# Schematic.net
KiCad netlist of a schematic drawn in Altium Designer
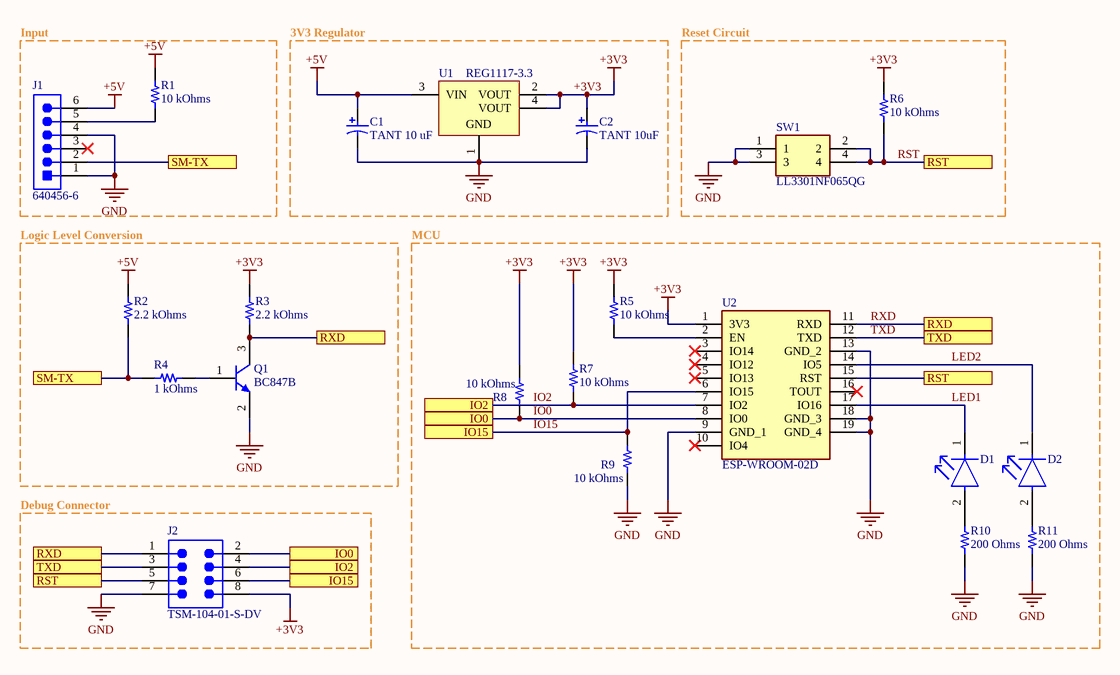
[diagram p0: Schematic.SchDoc]

(export (version "E")
  (design (tool "Eeschema 10.0.6"))
  (components
    (comp (ref "C1")
      (value "TANT 10 uF")
      (footprint "CAPMP3217X18-T_V")
      (description "Standard Tantalum, 10 uF, +/- 10%, 16 V, -55 to 125 degC, 2-Pin SMD (1206), RoHS, Tape and Reel")
      (libsource (lib "Altium Content Vault") (part "CAP-P-2"))
    )
    (comp (ref "C2")
      (value "TANT 10uF")
      (footprint "CAPMP3217X18-T_V")
      (description "Standard Tantalum, 10 uF, +/- 10%, 16 V, -55 to 125 degC, 2-Pin SMD (1206), RoHS, Tape and Reel")
      (libsource (lib "Altium Content Vault") (part "CAP-P-2"))
    )
    (comp (ref "D1")
      (value "LTST-C190GKT")
      (footprint "FP-LTST-C190GKT-MFG")
      (description "LED GREEN CLEAR CHIP SMD")
      (fields (field (name "VOLTAGE") "2V"))
      (libsource (lib "Altium Content Vault") (part "8706943c75ba83719d021d2fdc84c58"))
    )
    (comp (ref "D2")
      (value "LTST-C190GKT")
      (footprint "FP-LTST-C190GKT-MFG")
      (description "LED GREEN CLEAR CHIP SMD")
      (fields (field (name "VOLTAGE") "2V"))
      (libsource (lib "Altium Content Vault") (part "8706943c75ba83719d021d2fdc84c58"))
    )
    (comp (ref "J1")
      (value "640456-6")
      (footprint "TECO-640456-6_V")
      (fields (field (name "MANUFACTURER") "TE Connectivity"))
      (libsource (lib "Altium Content Vault") (part "CN-1P-M-R6"))
    )
    (comp (ref "J2")
      (value "TSM-104-01-S-DV")
      (footprint "SMTC-TSM-104-01-X-DV")
      (description "0.025\" SQ Post Header, Surface Mount, Vertical, -55 to 125 degC, 2.54 mm Pitch, 8-Pin, Male, RoHS")
      (fields (field (name "MANUFACTURER") "Samtec"))
      (libsource (lib "Altium Content Vault") (part "SMTC-TSM-104-01-X-X"))
    )
    (comp (ref "Q1")
      (value "BC847B")
      (footprint "INF-SOT23_M")
      (description "NPN Silicon AF Transistor, 45 V VCEO, 100 mA IC, SOT23, Reel, Green")
      (fields (field (name "MANUFACTURER") "Infineon"))
      (libsource (lib "Altium Content Vault") (part "INF-BJTNPN-BEC-3"))
    )
    (comp (ref "R1")
      (value "10 kOhms")
      (footprint "RES 0805_2012")
      (description "RES 10K OHM 0.1% 1/10W 0805")
      (fields
        (field (name "PART NUMBER") "RNCS0805BKE10K0")
        (field (name "MANUFACTURER") "Stackpole Electronics Inc")
      )
      (libsource (lib "Celestial Altium Library - altium_library") (part "Resistor"))
    )
    (comp (ref "R2")
      (value "2.2 kOhms")
      (footprint "RES 0805_2012")
      (description "RES SMD 2.2K OHM 5% 1/4W 0805")
      (fields (field (name "PART NUMBER") "SR0805JR-7W2K2L") (field (name "MANUFACTURER") "Yageo"))
      (libsource (lib "Celestial Altium Library - altium_library") (part "Resistor"))
    )
    (comp (ref "R3")
      (value "2.2 kOhms")
      (footprint "RES 0805_2012")
      (description "RES SMD 2.2K OHM 5% 1/4W 0805")
      (fields (field (name "PART NUMBER") "SR0805JR-7W2K2L") (field (name "MANUFACTURER") "Yageo"))
      (libsource (lib "Celestial Altium Library - altium_library") (part "Resistor"))
    )
    (comp (ref "R4")
      (value "1 kOhms")
      (footprint "RES 0805_2012")
      (description "RES 1K OHM 0.1% 1/10W 0805")
      (fields
        (field (name "PART NUMBER") "RNCS0805BKE1K00")
        (field (name "MANUFACTURER") "Stackpole Electronics Inc")
      )
      (libsource (lib "Celestial Altium Library - altium_library") (part "Resistor"))
    )
    (comp (ref "R5")
      (value "10 kOhms")
      (footprint "RES 0805_2012")
      (description "RES 10K OHM 0.1% 1/10W 0805")
      (fields
        (field (name "PART NUMBER") "RNCS0805BKE10K0")
        (field (name "MANUFACTURER") "Stackpole Electronics Inc")
      )
      (libsource (lib "Celestial Altium Library - altium_library") (part "Resistor"))
    )
    (comp (ref "R6")
      (value "10 kOhms")
      (footprint "RES 0805_2012")
      (description "RES 10K OHM 0.1% 1/10W 0805")
      (fields
        (field (name "PART NUMBER") "RNCS0805BKE10K0")
        (field (name "MANUFACTURER") "Stackpole Electronics Inc")
      )
      (libsource (lib "Celestial Altium Library - altium_library") (part "Resistor"))
    )
    (comp (ref "R7")
      (value "10 kOhms")
      (footprint "RES 0805_2012")
      (description "RES 10K OHM 0.1% 1/10W 0805")
      (fields
        (field (name "PART NUMBER") "RNCS0805BKE10K0")
        (field (name "MANUFACTURER") "Stackpole Electronics Inc")
      )
      (libsource (lib "Celestial Altium Library - altium_library") (part "Resistor"))
    )
    (comp (ref "R8")
      (value "10 kOhms")
      (footprint "RES 0805_2012")
      (description "RES 10K OHM 0.1% 1/10W 0805")
      (fields
        (field (name "PART NUMBER") "RNCS0805BKE10K0")
        (field (name "MANUFACTURER") "Stackpole Electronics Inc")
      )
      (libsource (lib "Celestial Altium Library - altium_library") (part "Resistor"))
    )
    (comp (ref "R9")
      (value "10 kOhms")
      (footprint "RES 0805_2012")
      (description "RES 10K OHM 0.1% 1/10W 0805")
      (fields
        (field (name "PART NUMBER") "RNCS0805BKE10K0")
        (field (name "MANUFACTURER") "Stackpole Electronics Inc")
      )
      (libsource (lib "Celestial Altium Library - altium_library") (part "Resistor"))
    )
    (comp (ref "R10")
      (value "200 Ohms")
      (footprint "RES 0805_2012")
      (description "RES SMD 200 OHM 0.5% 1/4W 0805")
      (fields
        (field (name "PART NUMBER") "ERJ-PB6D2000V")
        (field (name "MANUFACTURER") "Panasonic Electronic Components")
      )
      (libsource (lib "Celestial Altium Library - altium_library") (part "Resistor"))
    )
    (comp (ref "R11")
      (value "200 Ohms")
      (footprint "RES 0805_2012")
      (description "RES SMD 200 OHM 0.5% 1/4W 0805")
      (fields
        (field (name "PART NUMBER") "ERJ-PB6D2000V")
        (field (name "MANUFACTURER") "Panasonic Electronic Components")
      )
      (libsource (lib "Celestial Altium Library - altium_library") (part "Resistor"))
    )
    (comp (ref "SW1")
      (value "LL3301NF065QG")
      (footprint "SamacSys:LL3301NF065QG")
      (description "Switch")
      (fields (field (name "MOUSER2 PART NUMBER") "612-LL3301NF065QG"))
      (libsource (lib "SamacSys") (part "LL3301NF065QG"))
    )
    (comp (ref "U1")
      (value "REG1117-3.3")
      (footprint "DCY0004A_M")
      (fields (field (name "MANUFACTURER") "Texas Instruments"))
      (libsource (lib "Altium Content Vault") (part "TI-REG1117-XXXX"))
    )
    (comp (ref "U2")
      (value "ESP-WROOM-02D")
      (footprint "SamacSys:ESPWROOM02DM1102H3200PH3Q0")
      (description "Integrated Circuit")
      (fields (field (name "MANUFACTURER_PART_NUMBER") "ESP-WROOM-02D(M1102H3200PH3Q0)"))
      (libsource (lib "*") (part "ESP-WROOM-02D_M1102H3200PH3Q0_"))
    )
  )
  (nets
    (net (code "1") (name "+3V3") (class "Default")
      (node (ref "C2") (pin "1") (pinfunction "1_1") (pintype "passive"))
      (node (ref "J2") (pin "8") (pinfunction "8_8") (pintype "passive"))
      (node (ref "R3") (pin "2") (pinfunction "2_2") (pintype "passive"))
      (node (ref "R5") (pin "2") (pinfunction "2_2") (pintype "passive"))
      (node (ref "R6") (pin "2") (pinfunction "2_2") (pintype "passive"))
      (node (ref "R7") (pin "2") (pinfunction "2_2") (pintype "passive"))
      (node (ref "R8") (pin "2") (pinfunction "2_2") (pintype "passive"))
      (node (ref "U1") (pin "2") (pinfunction "VOUT_2") (pintype "power_in"))
      (node (ref "U1") (pin "4") (pinfunction "VOUT_4") (pintype "power_in"))
      (node (ref "U2") (pin "1") (pinfunction "3V3_1") (pintype "passive"))
    )
    (net (code "2") (name "+5V") (class "Default")
      (node (ref "C1") (pin "1") (pinfunction "1_1") (pintype "passive"))
      (node (ref "J1") (pin "6") (pinfunction "6_6") (pintype "passive"))
      (node (ref "R1") (pin "2") (pinfunction "2_2") (pintype "passive"))
      (node (ref "R2") (pin "2") (pinfunction "2_2") (pintype "passive"))
      (node (ref "U1") (pin "3") (pinfunction "VIN_3") (pintype "power_in"))
    )
    (net (code "3") (name "/IO0") (class "Default")
      (node (ref "J2") (pin "2") (pinfunction "2_2") (pintype "passive"))
      (node (ref "R8") (pin "1") (pinfunction "1_1") (pintype "passive"))
      (node (ref "U2") (pin "8") (pinfunction "IO0_8") (pintype "passive"))
    )
    (net (code "4") (name "/IO2") (class "Default")
      (node (ref "J2") (pin "4") (pinfunction "4_4") (pintype "passive"))
      (node (ref "R7") (pin "1") (pinfunction "1_1") (pintype "passive"))
      (node (ref "U2") (pin "7") (pinfunction "IO2_7") (pintype "passive"))
    )
    (net (code "5") (name "/IO15") (class "Default")
      (node (ref "J2") (pin "6") (pinfunction "6_6") (pintype "passive"))
      (node (ref "R9") (pin "2") (pinfunction "2_2") (pintype "passive"))
      (node (ref "U2") (pin "6") (pinfunction "IO15_6") (pintype "passive"))
    )
    (net (code "6") (name "/LED1") (class "Default")
      (node (ref "D1") (pin "1") (pinfunction "C_1") (pintype "passive"))
      (node (ref "U2") (pin "17") (pinfunction "IO16_17") (pintype "passive"))
    )
    (net (code "7") (name "/LED2") (class "Default")
      (node (ref "D2") (pin "1") (pinfunction "C_1") (pintype "passive"))
      (node (ref "U2") (pin "14") (pinfunction "IO5_14") (pintype "passive"))
    )
    (net (code "8") (name "/RST") (class "Default")
      (node (ref "J2") (pin "5") (pinfunction "5_5") (pintype "passive"))
      (node (ref "R6") (pin "1") (pinfunction "1_1") (pintype "passive"))
      (node (ref "SW1") (pin "2") (pinfunction "2_2") (pintype "passive"))
      (node (ref "SW1") (pin "4") (pinfunction "4_4") (pintype "passive"))
      (node (ref "U2") (pin "15") (pinfunction "RST_15") (pintype "passive"))
    )
    (net (code "9") (name "/RXD") (class "Default")
      (node (ref "J2") (pin "1") (pinfunction "1_1") (pintype "passive"))
      (node (ref "Q1") (pin "3") (pinfunction "C_3") (pintype "passive"))
      (node (ref "R3") (pin "1") (pinfunction "1_1") (pintype "passive"))
      (node (ref "U2") (pin "11") (pinfunction "RXD_11") (pintype "passive"))
    )
    (net (code "10") (name "/SM-TX") (class "Default")
      (node (ref "J1") (pin "2") (pinfunction "2_2") (pintype "passive"))
      (node (ref "R2") (pin "1") (pinfunction "1_1") (pintype "passive"))
      (node (ref "R4") (pin "1") (pinfunction "1_1") (pintype "passive"))
    )
    (net (code "11") (name "/TXD") (class "Default")
      (node (ref "J2") (pin "3") (pinfunction "3_3") (pintype "passive"))
      (node (ref "U2") (pin "12") (pinfunction "TXD_12") (pintype "passive"))
    )
    (net (code "12") (name "GND") (class "Default")
      (node (ref "C1") (pin "2") (pinfunction "2_2") (pintype "passive"))
      (node (ref "C2") (pin "2") (pinfunction "2_2") (pintype "passive"))
      (node (ref "J1") (pin "1") (pinfunction "1_1") (pintype "passive"))
      (node (ref "J1") (pin "4") (pinfunction "4_4") (pintype "passive"))
      (node (ref "J2") (pin "7") (pinfunction "7_7") (pintype "passive"))
      (node (ref "Q1") (pin "2") (pinfunction "E_2") (pintype "passive"))
      (node (ref "R10") (pin "1") (pinfunction "1_1") (pintype "passive"))
      (node (ref "R11") (pin "1") (pinfunction "1_1") (pintype "passive"))
      (node (ref "R9") (pin "1") (pinfunction "1_1") (pintype "passive"))
      (node (ref "SW1") (pin "1") (pinfunction "1_1") (pintype "passive"))
      (node (ref "SW1") (pin "3") (pinfunction "3_3") (pintype "passive"))
      (node (ref "U1") (pin "1") (pinfunction "GND_1") (pintype "power_in"))
      (node (ref "U2") (pin "13") (pinfunction "GND_2_13") (pintype "passive"))
      (node (ref "U2") (pin "18") (pinfunction "GND_3_18") (pintype "passive"))
      (node (ref "U2") (pin "19") (pinfunction "GND_4_19") (pintype "passive"))
      (node (ref "U2") (pin "9") (pinfunction "GND_1_9") (pintype "passive"))
    )
    (net (code "13") (name "Net-(D1-A)") (class "Default")
      (node (ref "D1") (pin "2") (pinfunction "A_2") (pintype "passive"))
      (node (ref "R10") (pin "2") (pinfunction "2_2") (pintype "passive"))
    )
    (net (code "14") (name "Net-(D2-A)") (class "Default")
      (node (ref "D2") (pin "2") (pinfunction "A_2") (pintype "passive"))
      (node (ref "R11") (pin "2") (pinfunction "2_2") (pintype "passive"))
    )
    (net (code "15") (name "Net-(J1-Pad5)") (class "Default")
      (node (ref "J1") (pin "5") (pinfunction "5_5") (pintype "passive"))
      (node (ref "R1") (pin "1") (pinfunction "1_1") (pintype "passive"))
    )
    (net (code "16") (name "Net-(Q1-B)") (class "Default")
      (node (ref "Q1") (pin "1") (pinfunction "B_1") (pintype "passive"))
      (node (ref "R4") (pin "2") (pinfunction "2_2") (pintype "passive"))
    )
    (net (code "17") (name "Net-(U2-EN)") (class "Default")
      (node (ref "R5") (pin "1") (pinfunction "1_1") (pintype "passive"))
      (node (ref "U2") (pin "2") (pinfunction "EN_2") (pintype "passive"))
    )
    (net (code "18") (name "unconnected-(J1-Pad3)") (class "Default")
      (node (ref "J1") (pin "3") (pinfunction "3_3") (pintype "passive+no_connect"))
    )
    (net (code "19") (name "unconnected-(U2-IO4-Pad10)") (class "Default")
      (node (ref "U2") (pin "10") (pinfunction "IO4_10") (pintype "passive+no_connect"))
    )
    (net (code "20") (name "unconnected-(U2-IO12-Pad4)") (class "Default")
      (node (ref "U2") (pin "4") (pinfunction "IO12_4") (pintype "passive+no_connect"))
    )
    (net (code "21") (name "unconnected-(U2-IO13-Pad5)") (class "Default")
      (node (ref "U2") (pin "5") (pinfunction "IO13_5") (pintype "passive+no_connect"))
    )
    (net (code "22") (name "unconnected-(U2-IO14-Pad3)") (class "Default")
      (node (ref "U2") (pin "3") (pinfunction "IO14_3") (pintype "passive+no_connect"))
    )
    (net (code "23") (name "unconnected-(U2-TOUT-Pad16)") (class "Default")
      (node (ref "U2") (pin "16") (pinfunction "TOUT_16") (pintype "passive+no_connect"))
    )
  )
)
